# F_Antenna.net
KiCad netlist of a schematic drawn in Altium Designer
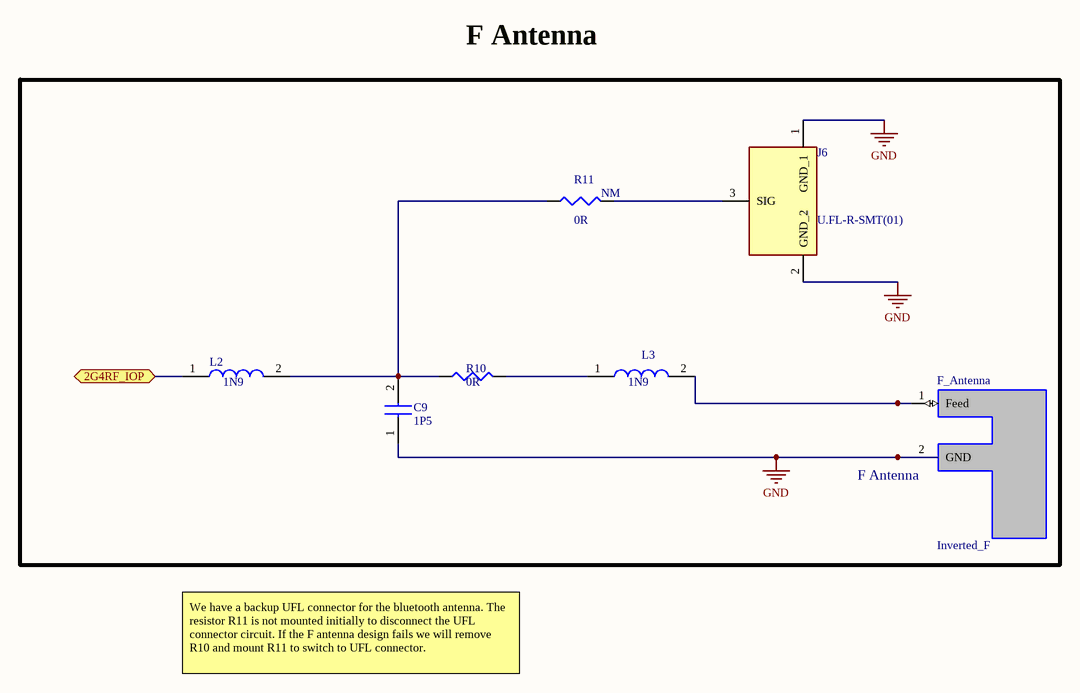
[diagram p0: F_Antenna.SchDoc]

(export (version "E")
  (design (tool "Eeschema 10.0.6"))
  (components
    (comp (ref "C9")
      (value "1P5")
      (footprint "SamacSys:CAPC1005X55N")
      (description "Capacitor")
      (fields
        (field (name "MANUFACTURER_PART_NUMBER") "GRM1555C1H1R5WA01D")
        (field (name "MOUSER PART NUMBER") "81-GRM1555C1H1R5WA1D")
      )
      (libsource (lib "*") (part "GRM1555C1H1R5WA01D"))
    )
    (comp (ref "F_Antenna")
      (value "Inverted_F")
      (footprint "Inverted_F")
      (libsource (lib "EFR32BG13P632F512GM48") (part "Inverted_F"))
    )
    (comp (ref "J6")
      (value "U.FL-R-SMT(01)")
      (footprint "SamacSys:U.FL-R-SMT(01)")
      (description "Connector")
      (fields
        (field (name "MOUSER PART NUMBER") "798-U.FL-R-SMT01")
        (field (name "RS PART NUMBER") "4812324P")
      )
      (libsource (lib "*") (part "U.FL-R-SMT(01)"))
    )
    (comp (ref "L2")
      (value "1N9")
      (footprint "SamacSys:INDC1005X45N")
      (description "Inductor")
      (fields
        (field (name "MANUFACTURER_PART_NUMBER") "LQP15MN1N9W02D")
        (field (name "MOUSER PART NUMBER") "81-LQP15MN1N9W02D")
      )
      (libsource (lib "*") (part "LQP15MN1N9W02D"))
    )
    (comp (ref "L3")
      (value "1N9")
      (footprint "SamacSys:INDC1005X45N")
      (description "Inductor")
      (fields
        (field (name "MANUFACTURER_PART_NUMBER") "LQP15MN1N9W02D")
        (field (name "MOUSER PART NUMBER") "81-LQP15MN1N9W02D")
      )
      (libsource (lib "*") (part "LQP15MN1N9W02D"))
    )
    (comp (ref "R10")
      (value "0R")
      (footprint "J1-0603")
      (description "Resistor")
      (fields
        (field (name "DIGI-KEY PART NUMBER") "541-0.0SBCT-ND")
        (field (name "MANUFACTURER_PART_NUMBER") "CRCW06030000Z0EAHP")
      )
      (libsource (lib "Miscellaneous Devices") (part "Res3"))
    )
    (comp (ref "R11")
      (value "0R")
      (footprint "J1-0603")
      (description "Resistor")
      (fields
        (field (name "DIGI-KEY PART NUMBER") "541-0.0SBCT-ND")
        (field (name "MANUFACTURER_PART_NUMBER") "CRCW06030000Z0EAHP")
        (field (name "MOUNTED") "NM")
      )
      (libsource (lib "Miscellaneous Devices") (part "Res3"))
    )
  )
  (nets
    (net (code "1") (name "/2G4RF_IOP") (class "Default")
      (node (ref "L2") (pin "1") (pinfunction "1_1") (pintype "passive"))
    )
    (net (code "2") (name "GND") (class "Default")
      (node (ref "C9") (pin "1") (pinfunction "1_1") (pintype "passive"))
      (node (ref "F_Antenna") (pin "2") (pinfunction "GND_2") (pintype "power_in"))
      (node (ref "J6") (pin "1") (pinfunction "GND_1_1") (pintype "passive"))
      (node (ref "J6") (pin "2") (pinfunction "GND_2_2") (pintype "passive"))
    )
    (net (code "3") (name "Net-(C9-Pad2)") (class "Default")
      (node (ref "C9") (pin "2") (pinfunction "2_2") (pintype "passive"))
      (node (ref "L2") (pin "2") (pinfunction "2_2") (pintype "passive"))
      (node (ref "R10") (pin "1") (pinfunction "1_1") (pintype "passive"))
      (node (ref "R11") (pin "1") (pinfunction "1_1") (pintype "passive"))
    )
    (net (code "4") (name "Net-(F_Antenna-Feed)") (class "Default")
      (node (ref "F_Antenna") (pin "1") (pinfunction "Feed_1") (pintype "bidirectional"))
      (node (ref "L3") (pin "2") (pinfunction "2_2") (pintype "passive"))
    )
    (net (code "5") (name "Net-(J6-SIG)") (class "Default")
      (node (ref "J6") (pin "3") (pinfunction "SIG_3") (pintype "passive"))
      (node (ref "R11") (pin "2") (pinfunction "2_2") (pintype "passive"))
    )
    (net (code "6") (name "Net-(L3-Pad1)") (class "Default")
      (node (ref "L3") (pin "1") (pinfunction "1_1") (pintype "passive"))
      (node (ref "R10") (pin "2") (pinfunction "2_2") (pintype "passive"))
    )
  )
)
